# 16segclock.net
KiCad netlist of a schematic drawn in EAGLE
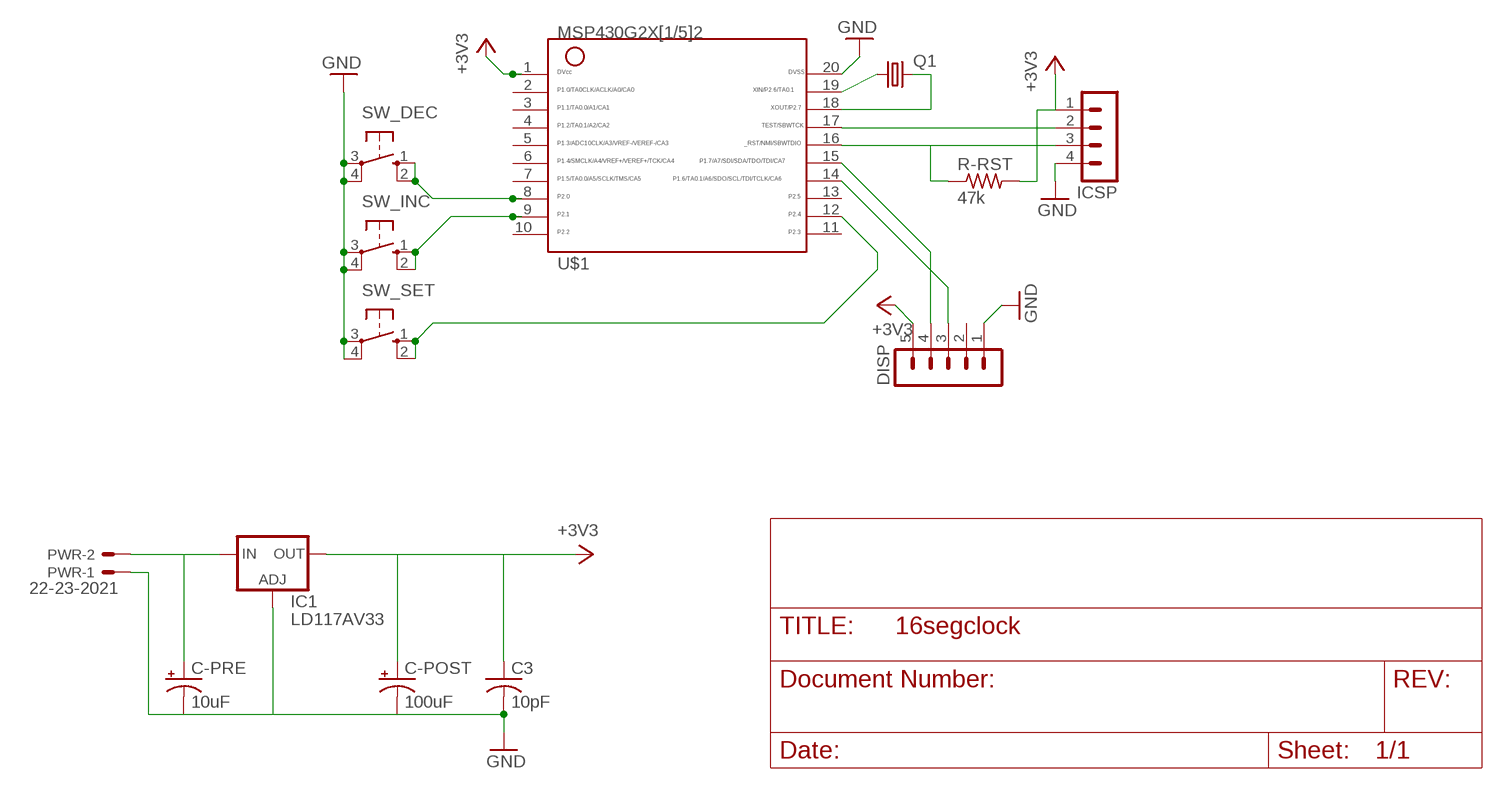
[diagram p0: schematic, sheet 1]

(export (version "E")
  (design (tool "Eeschema 10.0.6"))
  (components
    (comp (ref "C-POST")
      (value "100uF")
      (footprint "eagle-import:E3,5-8")
      (libsource (lib "eagle-import") (part "CPOL-USE3.5-8"))
    )
    (comp (ref "C-PRE")
      (value "10uF")
      (footprint "eagle-import:E2,5-6")
      (libsource (lib "eagle-import") (part "CPOL-USE2.5-6"))
    )
    (comp (ref "C3")
      (value "10pF")
      (footprint "eagle-import:C0805")
      (libsource (lib "eagle-import") (part "C-USC0805"))
    )
    (comp (ref "DISP")
      (value "MA05-1")
      (footprint "eagle-import:MA05-1")
      (libsource (lib "eagle-import") (part "MA05-1"))
    )
    (comp (ref "IC1")
      (value "LD117AV33")
      (footprint "eagle-import:TO220L1")
      (libsource (lib "eagle-import") (part "LD117A?V33"))
    )
    (comp (ref "ICSP")
      (value "MA04-1")
      (footprint "eagle-import:MA04-1")
      (libsource (lib "eagle-import") (part "MA04-1"))
    )
    (comp (ref "PWR")
      (value "22-23-2021")
      (footprint "eagle-import:22-23-2021")
      (fields (field (name "MF") "MOLEX"))
      (libsource (lib "eagle-import") (part "22-23-2021"))
    )
    (comp (ref "Q1")
      (value "CRYSTALTC38H")
      (footprint "eagle-import:TC38H")
      (libsource (lib "eagle-import") (part "CRYSTALTC38H"))
    )
    (comp (ref "R-RST")
      (value "47k")
      (footprint "eagle-import:R0805")
      (libsource (lib "eagle-import") (part "R-US_R0805"))
    )
    (comp (ref "SW_DEC")
      (value "10-XX")
      (footprint "eagle-import:B3F-10XX")
      (fields (field (name "MPN") "B3F-1000"))
      (libsource (lib "eagle-import") (part "10-XX"))
    )
    (comp (ref "SW_INC")
      (value "10-XX")
      (footprint "eagle-import:B3F-10XX")
      (fields (field (name "MPN") "B3F-1000"))
      (libsource (lib "eagle-import") (part "10-XX"))
    )
    (comp (ref "SW_SET")
      (value "10-XX")
      (footprint "eagle-import:B3F-10XX")
      (fields (field (name "MPN") "B3F-1000"))
      (libsource (lib "eagle-import") (part "10-XX"))
    )
    (comp (ref "U$1")
      (value "G2X[1/5]2---N20")
      (footprint "eagle-import:N20")
      (libsource (lib "eagle-import") (part "G2X[1/5]2---N20"))
    )
  )
  (nets
    (net (code "1") (name "+3V3") (class "Default")
      (node (ref "C-POST") (pin "+") (pinfunction "+_+") (pintype "passive"))
      (node (ref "C3") (pin "1") (pinfunction "1_1") (pintype "passive"))
      (node (ref "DISP") (pin "5") (pinfunction "5_5") (pintype "passive"))
      (node (ref "IC1") (pin "2") (pinfunction "OUT_2") (pintype "passive"))
      (node (ref "ICSP") (pin "1") (pinfunction "1_1") (pintype "passive"))
      (node (ref "R-RST") (pin "2") (pinfunction "2_2") (pintype "passive"))
      (node (ref "U$1") (pin "1") (pinfunction "1_1") (pintype "bidirectional"))
    )
    (net (code "2") (name "GND") (class "Default")
      (node (ref "C-POST") (pin "-") (pinfunction "-_-") (pintype "passive"))
      (node (ref "C-PRE") (pin "-") (pinfunction "-_-") (pintype "passive"))
      (node (ref "C3") (pin "2") (pinfunction "2_2") (pintype "passive"))
      (node (ref "DISP") (pin "1") (pinfunction "1_1") (pintype "passive"))
      (node (ref "IC1") (pin "1") (pinfunction "ADJ_1") (pintype "input"))
      (node (ref "ICSP") (pin "4") (pinfunction "4_4") (pintype "passive"))
      (node (ref "PWR") (pin "1") (pinfunction "S_1") (pintype "passive"))
      (node (ref "SW_DEC") (pin "3") (pinfunction "P_3") (pintype "passive"))
      (node (ref "SW_DEC") (pin "4") (pinfunction "P1_4") (pintype "passive"))
      (node (ref "SW_INC") (pin "3") (pinfunction "P_3") (pintype "passive"))
      (node (ref "SW_INC") (pin "4") (pinfunction "P1_4") (pintype "passive"))
      (node (ref "SW_SET") (pin "3") (pinfunction "P_3") (pintype "passive"))
      (node (ref "SW_SET") (pin "4") (pinfunction "P1_4") (pintype "passive"))
      (node (ref "U$1") (pin "20") (pinfunction "20_20") (pintype "bidirectional"))
    )
    (net (code "3") (name "Net-(DISP-Pad3)") (class "Default")
      (node (ref "DISP") (pin "3") (pinfunction "3_3") (pintype "passive"))
      (node (ref "U$1") (pin "14") (pinfunction "14_14") (pintype "bidirectional"))
    )
    (net (code "4") (name "Net-(DISP-Pad4)") (class "Default")
      (node (ref "DISP") (pin "4") (pinfunction "4_4") (pintype "passive"))
      (node (ref "U$1") (pin "15") (pinfunction "15_15") (pintype "bidirectional"))
    )
    (net (code "5") (name "Net-(IC1-IN)") (class "Default")
      (node (ref "C-PRE") (pin "+") (pinfunction "+_+") (pintype "passive"))
      (node (ref "IC1") (pin "3") (pinfunction "IN_3") (pintype "input"))
      (node (ref "PWR") (pin "2") (pinfunction "S_2") (pintype "passive"))
    )
    (net (code "6") (name "Net-(ICSP-Pad2)") (class "Default")
      (node (ref "ICSP") (pin "2") (pinfunction "2_2") (pintype "passive"))
      (node (ref "U$1") (pin "17") (pinfunction "17_17") (pintype "bidirectional"))
    )
    (net (code "7") (name "Net-(ICSP-Pad3)") (class "Default")
      (node (ref "ICSP") (pin "3") (pinfunction "3_3") (pintype "passive"))
      (node (ref "R-RST") (pin "1") (pinfunction "1_1") (pintype "passive"))
      (node (ref "U$1") (pin "16") (pinfunction "16_16") (pintype "bidirectional"))
    )
    (net (code "8") (name "Net-(Q1-Pad1)") (class "Default")
      (node (ref "Q1") (pin "1") (pinfunction "1_1") (pintype "passive"))
      (node (ref "U$1") (pin "19") (pinfunction "19_19") (pintype "bidirectional"))
    )
    (net (code "9") (name "Net-(Q1-Pad2)") (class "Default")
      (node (ref "Q1") (pin "2") (pinfunction "2_2") (pintype "passive"))
      (node (ref "U$1") (pin "18") (pinfunction "18_18") (pintype "bidirectional"))
    )
    (net (code "10") (name "Net-(SW_DEC-S)") (class "Default")
      (node (ref "SW_DEC") (pin "1") (pinfunction "S_1") (pintype "passive"))
      (node (ref "SW_DEC") (pin "2") (pinfunction "S1_2") (pintype "passive"))
      (node (ref "U$1") (pin "8") (pinfunction "8_8") (pintype "bidirectional"))
    )
    (net (code "11") (name "Net-(SW_INC-S)") (class "Default")
      (node (ref "SW_INC") (pin "1") (pinfunction "S_1") (pintype "passive"))
      (node (ref "SW_INC") (pin "2") (pinfunction "S1_2") (pintype "passive"))
      (node (ref "U$1") (pin "9") (pinfunction "9_9") (pintype "bidirectional"))
    )
    (net (code "12") (name "Net-(SW_SET-S)") (class "Default")
      (node (ref "SW_SET") (pin "1") (pinfunction "S_1") (pintype "passive"))
      (node (ref "SW_SET") (pin "2") (pinfunction "S1_2") (pintype "passive"))
      (node (ref "U$1") (pin "12") (pinfunction "12_12") (pintype "bidirectional"))
    )
    (net (code "13") (name "unconnected-(DISP-Pad2)") (class "Default")
      (node (ref "DISP") (pin "2") (pinfunction "2_2") (pintype "passive"))
    )
    (net (code "14") (name "unconnected-(U$1-Pad2)") (class "Default")
      (node (ref "U$1") (pin "2") (pinfunction "2_2") (pintype "bidirectional"))
    )
    (net (code "15") (name "unconnected-(U$1-Pad3)") (class "Default")
      (node (ref "U$1") (pin "3") (pinfunction "3_3") (pintype "bidirectional"))
    )
    (net (code "16") (name "unconnected-(U$1-Pad4)") (class "Default")
      (node (ref "U$1") (pin "4") (pinfunction "4_4") (pintype "bidirectional"))
    )
    (net (code "17") (name "unconnected-(U$1-Pad5)") (class "Default")
      (node (ref "U$1") (pin "5") (pinfunction "5_5") (pintype "bidirectional"))
    )
    (net (code "18") (name "unconnected-(U$1-Pad6)") (class "Default")
      (node (ref "U$1") (pin "6") (pinfunction "6_6") (pintype "bidirectional"))
    )
    (net (code "19") (name "unconnected-(U$1-Pad7)") (class "Default")
      (node (ref "U$1") (pin "7") (pinfunction "7_7") (pintype "bidirectional"))
    )
    (net (code "20") (name "unconnected-(U$1-Pad10)") (class "Default")
      (node (ref "U$1") (pin "10") (pinfunction "10_10") (pintype "bidirectional"))
    )
    (net (code "21") (name "unconnected-(U$1-Pad11)") (class "Default")
      (node (ref "U$1") (pin "11") (pinfunction "11_11") (pintype "bidirectional"))
    )
    (net (code "22") (name "unconnected-(U$1-Pad13)") (class "Default")
      (node (ref "U$1") (pin "13") (pinfunction "13_13") (pintype "bidirectional"))
    )
  )
)
